# sensorOscillator02_v02.net
KiCad netlist of a schematic drawn in EAGLE
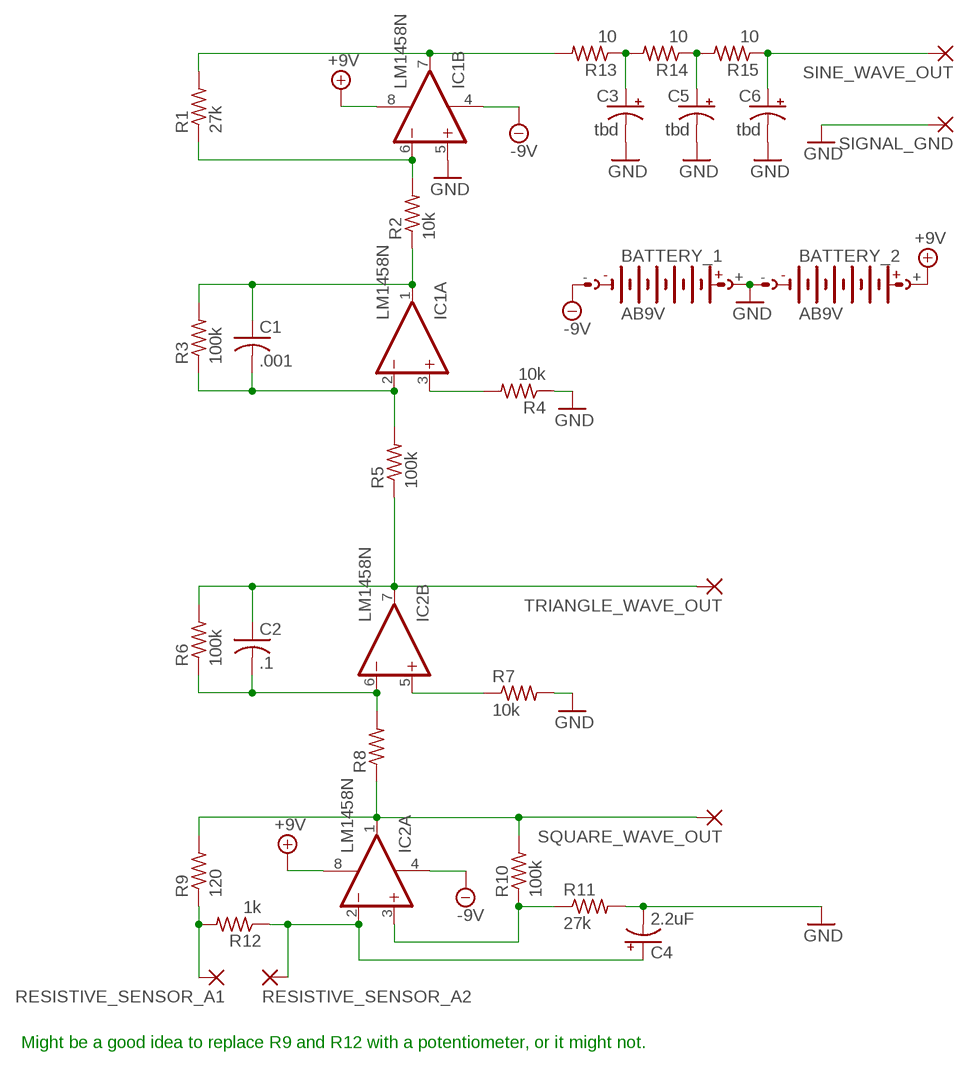
[diagram p0: schematic, sheet 1]

(export (version "E")
  (design (tool "Eeschema 10.0.6"))
  (components
    (comp (ref "BATTERY_1")
      (value "AB9V")
      (footprint "eagle-import:AB9V")
      (libsource (lib "eagle-import") (part "AB9V"))
    )
    (comp (ref "BATTERY_2")
      (value "AB9V")
      (footprint "eagle-import:AB9V")
      (libsource (lib "eagle-import") (part "AB9V"))
    )
    (comp (ref "C1")
      (value ".001")
      (footprint "eagle-import:C075-063X106")
      (libsource (lib "eagle-import") (part "C-US075-063X106"))
    )
    (comp (ref "C2")
      (value ".1")
      (footprint "eagle-import:C075-063X106")
      (libsource (lib "eagle-import") (part "C-US075-063X106"))
    )
    (comp (ref "C3")
      (value "tbd")
      (footprint "eagle-import:E5-5")
      (libsource (lib "eagle-import") (part "CPOL-USE5-5"))
    )
    (comp (ref "C4")
      (value "2.2uF")
      (footprint "eagle-import:E5-5")
      (libsource (lib "eagle-import") (part "CPOL-USE5-5"))
    )
    (comp (ref "C5")
      (value "tbd")
      (footprint "eagle-import:E5-5")
      (libsource (lib "eagle-import") (part "CPOL-USE5-5"))
    )
    (comp (ref "C6")
      (value "tbd")
      (footprint "eagle-import:E5-5")
      (libsource (lib "eagle-import") (part "CPOL-USE5-5"))
    )
    (comp (ref "IC1")
      (value "LM1458N")
      (footprint "eagle-import:DIL08")
      (libsource (lib "eagle-import") (part "1458NLM"))
    )
    (comp (ref "IC2")
      (value "LM1458N")
      (footprint "eagle-import:DIL08")
      (libsource (lib "eagle-import") (part "1458NLM"))
    )
    (comp (ref "R1")
      (value "27k")
      (footprint "eagle-import:0411_12")
      (libsource (lib "eagle-import") (part "R-US_0411/12"))
    )
    (comp (ref "R2")
      (value "10k")
      (footprint "eagle-import:0411_12")
      (libsource (lib "eagle-import") (part "R-US_0411/12"))
    )
    (comp (ref "R3")
      (value "100k")
      (footprint "eagle-import:0411_12")
      (libsource (lib "eagle-import") (part "R-US_0411/12"))
    )
    (comp (ref "R4")
      (value "10k")
      (footprint "eagle-import:0411_12")
      (libsource (lib "eagle-import") (part "R-US_0411/12"))
    )
    (comp (ref "R5")
      (value "100k")
      (footprint "eagle-import:0411_12")
      (libsource (lib "eagle-import") (part "R-US_0411/12"))
    )
    (comp (ref "R6")
      (value "100k")
      (footprint "eagle-import:0411_12")
      (libsource (lib "eagle-import") (part "R-US_0411/12"))
    )
    (comp (ref "R7")
      (value "10k")
      (footprint "eagle-import:0411_12")
      (libsource (lib "eagle-import") (part "R-US_0411/12"))
    )
    (comp (ref "R8")
      (value "R-US_0411/12")
      (footprint "eagle-import:0411_12")
      (libsource (lib "eagle-import") (part "R-US_0411/12"))
    )
    (comp (ref "R9")
      (value "120")
      (footprint "eagle-import:0411_12")
      (libsource (lib "eagle-import") (part "R-US_0411/12"))
    )
    (comp (ref "R10")
      (value "100k")
      (footprint "eagle-import:0411_12")
      (libsource (lib "eagle-import") (part "R-US_0411/12"))
    )
    (comp (ref "R11")
      (value "27k")
      (footprint "eagle-import:0411_12")
      (libsource (lib "eagle-import") (part "R-US_0411/12"))
    )
    (comp (ref "R12")
      (value "1k")
      (footprint "eagle-import:0411_12")
      (libsource (lib "eagle-import") (part "R-US_0411/12"))
    )
    (comp (ref "R13")
      (value "10")
      (footprint "eagle-import:0411_12")
      (libsource (lib "eagle-import") (part "R-US_0411/12"))
    )
    (comp (ref "R14")
      (value "10")
      (footprint "eagle-import:0411_12")
      (libsource (lib "eagle-import") (part "R-US_0411/12"))
    )
    (comp (ref "R15")
      (value "10")
      (footprint "eagle-import:0411_12")
      (libsource (lib "eagle-import") (part "R-US_0411/12"))
    )
    (comp (ref "RESISTIVE_SENSOR_A1")
      (value "3,81/1,3")
      (footprint "eagle-import:3,81_1,3")
      (libsource (lib "eagle-import") (part "3,81/1,3"))
    )
    (comp (ref "RESISTIVE_SENSOR_A2")
      (value "3,81/1,3")
      (footprint "eagle-import:3,81_1,3")
      (libsource (lib "eagle-import") (part "3,81/1,3"))
    )
    (comp (ref "SIGNAL_GND")
      (value "3,81/1,3")
      (footprint "eagle-import:3,81_1,3")
      (libsource (lib "eagle-import") (part "3,81/1,3"))
    )
    (comp (ref "SINE_WAVE_OUT")
      (value "3,81/1,3")
      (footprint "eagle-import:3,81_1,3")
      (libsource (lib "eagle-import") (part "3,81/1,3"))
    )
    (comp (ref "SQUARE_WAVE_OUT")
      (value "3,81/1,3")
      (footprint "eagle-import:3,81_1,3")
      (libsource (lib "eagle-import") (part "3,81/1,3"))
    )
    (comp (ref "TRIANGLE_WAVE_OUT")
      (value "3,81/1,3")
      (footprint "eagle-import:3,81_1,3")
      (libsource (lib "eagle-import") (part "3,81/1,3"))
    )
  )
  (nets
    (net (code "1") (name "+9V") (class "Default")
      (node (ref "BATTERY_2") (pin "+") (pinfunction "+_+") (pintype "passive"))
      (node (ref "IC1") (pin "8") (pinfunction "V+_8") (pintype "power_in"))
      (node (ref "IC2") (pin "8") (pinfunction "V+_8") (pintype "power_in"))
    )
    (net (code "2") (name "-9V") (class "Default")
      (node (ref "BATTERY_1") (pin "-") (pinfunction "-_-") (pintype "passive"))
      (node (ref "IC1") (pin "4") (pinfunction "V-_4") (pintype "power_in"))
      (node (ref "IC2") (pin "4") (pinfunction "V-_4") (pintype "power_in"))
    )
    (net (code "3") (name "GND") (class "Default")
      (node (ref "BATTERY_1") (pin "+") (pinfunction "+_+") (pintype "passive"))
      (node (ref "BATTERY_2") (pin "-") (pinfunction "-_-") (pintype "passive"))
      (node (ref "C3") (pin "-") (pinfunction "-_-") (pintype "passive"))
      (node (ref "C4") (pin "-") (pinfunction "-_-") (pintype "passive"))
      (node (ref "C5") (pin "-") (pinfunction "-_-") (pintype "passive"))
      (node (ref "C6") (pin "-") (pinfunction "-_-") (pintype "passive"))
      (node (ref "IC1") (pin "5") (pinfunction "+IN_5") (pintype "input"))
      (node (ref "R11") (pin "2") (pinfunction "2_2") (pintype "passive"))
      (node (ref "R4") (pin "1") (pinfunction "1_1") (pintype "passive"))
      (node (ref "R7") (pin "2") (pinfunction "2_2") (pintype "passive"))
      (node (ref "SIGNAL_GND") (pin "1") (pinfunction "P_1") (pintype "passive"))
    )
    (net (code "4") (name "Net-(C3-Pad+)") (class "Default")
      (node (ref "C3") (pin "+") (pinfunction "+_+") (pintype "passive"))
      (node (ref "R13") (pin "1") (pinfunction "1_1") (pintype "passive"))
      (node (ref "R14") (pin "2") (pinfunction "2_2") (pintype "passive"))
    )
    (net (code "5") (name "Net-(C5-Pad+)") (class "Default")
      (node (ref "C5") (pin "+") (pinfunction "+_+") (pintype "passive"))
      (node (ref "R14") (pin "1") (pinfunction "1_1") (pintype "passive"))
      (node (ref "R15") (pin "2") (pinfunction "2_2") (pintype "passive"))
    )
    (net (code "6") (name "Net-(IC1A-+IN)") (class "Default")
      (node (ref "IC1") (pin "3") (pinfunction "+IN_3") (pintype "input"))
      (node (ref "R4") (pin "2") (pinfunction "2_2") (pintype "passive"))
    )
    (net (code "7") (name "Net-(IC1A--IN)") (class "Default")
      (node (ref "C1") (pin "2") (pinfunction "2_2") (pintype "passive"))
      (node (ref "IC1") (pin "2") (pinfunction "-IN_2") (pintype "input"))
      (node (ref "R3") (pin "1") (pinfunction "1_1") (pintype "passive"))
      (node (ref "R5") (pin "2") (pinfunction "2_2") (pintype "passive"))
    )
    (net (code "8") (name "Net-(IC1A-OUT)") (class "Default")
      (node (ref "C1") (pin "1") (pinfunction "1_1") (pintype "passive"))
      (node (ref "IC1") (pin "1") (pinfunction "OUT_1") (pintype "output"))
      (node (ref "R2") (pin "1") (pinfunction "1_1") (pintype "passive"))
      (node (ref "R3") (pin "2") (pinfunction "2_2") (pintype "passive"))
    )
    (net (code "9") (name "Net-(IC1B--IN)") (class "Default")
      (node (ref "IC1") (pin "6") (pinfunction "-IN_6") (pintype "input"))
      (node (ref "R1") (pin "1") (pinfunction "1_1") (pintype "passive"))
      (node (ref "R2") (pin "2") (pinfunction "2_2") (pintype "passive"))
    )
    (net (code "10") (name "Net-(IC1B-OUT)") (class "Default")
      (node (ref "IC1") (pin "7") (pinfunction "OUT_7") (pintype "output"))
      (node (ref "R1") (pin "2") (pinfunction "2_2") (pintype "passive"))
      (node (ref "R13") (pin "2") (pinfunction "2_2") (pintype "passive"))
    )
    (net (code "11") (name "Net-(IC2A-+IN)") (class "Default")
      (node (ref "IC2") (pin "3") (pinfunction "+IN_3") (pintype "input"))
      (node (ref "R10") (pin "1") (pinfunction "1_1") (pintype "passive"))
      (node (ref "R11") (pin "1") (pinfunction "1_1") (pintype "passive"))
    )
    (net (code "12") (name "Net-(IC2A--IN)") (class "Default")
      (node (ref "C4") (pin "+") (pinfunction "+_+") (pintype "passive"))
      (node (ref "IC2") (pin "2") (pinfunction "-IN_2") (pintype "input"))
      (node (ref "R12") (pin "1") (pinfunction "1_1") (pintype "passive"))
      (node (ref "RESISTIVE_SENSOR_A2") (pin "1") (pinfunction "P_1") (pintype "passive"))
    )
    (net (code "13") (name "Net-(IC2A-OUT)") (class "Default")
      (node (ref "IC2") (pin "1") (pinfunction "OUT_1") (pintype "output"))
      (node (ref "R10") (pin "2") (pinfunction "2_2") (pintype "passive"))
      (node (ref "R8") (pin "1") (pinfunction "1_1") (pintype "passive"))
      (node (ref "R9") (pin "2") (pinfunction "2_2") (pintype "passive"))
      (node (ref "SQUARE_WAVE_OUT") (pin "1") (pinfunction "P_1") (pintype "passive"))
    )
    (net (code "14") (name "Net-(IC2B-+IN)") (class "Default")
      (node (ref "IC2") (pin "5") (pinfunction "+IN_5") (pintype "input"))
      (node (ref "R7") (pin "1") (pinfunction "1_1") (pintype "passive"))
    )
    (net (code "15") (name "Net-(IC2B--IN)") (class "Default")
      (node (ref "C2") (pin "2") (pinfunction "2_2") (pintype "passive"))
      (node (ref "IC2") (pin "6") (pinfunction "-IN_6") (pintype "input"))
      (node (ref "R6") (pin "1") (pinfunction "1_1") (pintype "passive"))
      (node (ref "R8") (pin "2") (pinfunction "2_2") (pintype "passive"))
    )
    (net (code "16") (name "Net-(IC2B-OUT)") (class "Default")
      (node (ref "C2") (pin "1") (pinfunction "1_1") (pintype "passive"))
      (node (ref "IC2") (pin "7") (pinfunction "OUT_7") (pintype "output"))
      (node (ref "R5") (pin "1") (pinfunction "1_1") (pintype "passive"))
      (node (ref "R6") (pin "2") (pinfunction "2_2") (pintype "passive"))
      (node (ref "TRIANGLE_WAVE_OUT") (pin "1") (pinfunction "P_1") (pintype "passive"))
    )
    (net (code "17") (name "Net-(RESISTIVE_SENSOR_A1-P)") (class "Default")
      (node (ref "R12") (pin "2") (pinfunction "2_2") (pintype "passive"))
      (node (ref "R9") (pin "1") (pinfunction "1_1") (pintype "passive"))
      (node (ref "RESISTIVE_SENSOR_A1") (pin "1") (pinfunction "P_1") (pintype "passive"))
    )
    (net (code "18") (name "Net-(SINE_WAVE_OUT-P)") (class "Default")
      (node (ref "C6") (pin "+") (pinfunction "+_+") (pintype "passive"))
      (node (ref "R15") (pin "1") (pinfunction "1_1") (pintype "passive"))
      (node (ref "SINE_WAVE_OUT") (pin "1") (pinfunction "P_1") (pintype "passive"))
    )
  )
)
